# tfcard_shield.net
KiCad netlist of a schematic drawn in Altium Designer
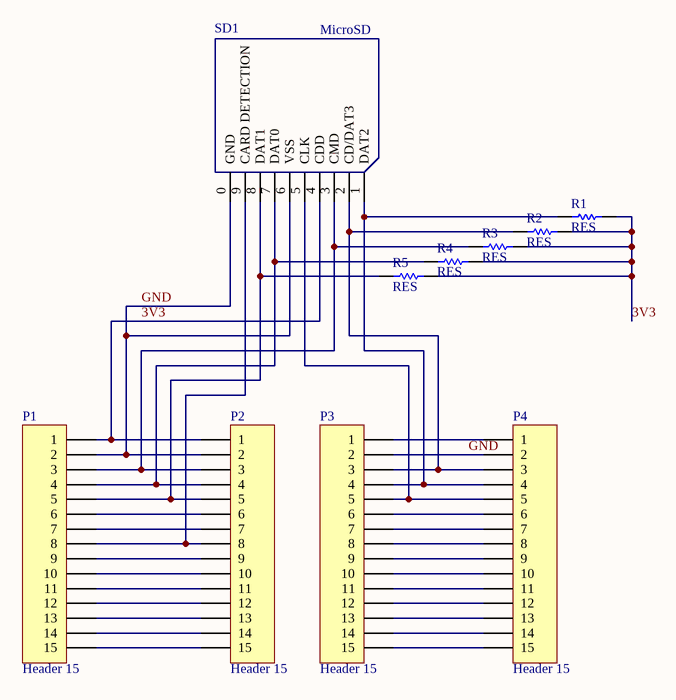
[diagram p0: tfcard_shield.SchDoc]

(export (version "E")
  (design (tool "Eeschema 10.0.6"))
  (components
    (comp (ref "P1")
      (value "Header 15")
      (footprint "HDR1X15")
      (description "Header, 15-Pin")
      (fields (field (name "PUBLISHER") "Altium Limited"))
      (libsource (lib "") (part "Header 15_1"))
    )
    (comp (ref "P2")
      (value "Header 15")
      (footprint "HDR1X15")
      (description "Header, 15-Pin")
      (fields (field (name "PUBLISHER") "Altium Limited"))
      (libsource (lib "Miscellaneous Connectors") (part "Header 15"))
    )
    (comp (ref "P3")
      (value "Header 15")
      (footprint "HDR1X15")
      (description "Header, 15-Pin")
      (fields (field (name "PUBLISHER") "Altium Limited"))
      (libsource (lib "") (part "Header 15_1"))
    )
    (comp (ref "P4")
      (value "Header 15")
      (footprint "HDR1X15")
      (description "Header, 15-Pin")
      (fields (field (name "PUBLISHER") "Altium Limited"))
      (libsource (lib "Miscellaneous Connectors") (part "Header 15"))
    )
    (comp (ref "R1") (value "RES") (footprint "0603R") (libsource (lib "电阻") (part "RES")))
    (comp (ref "R2") (value "RES") (footprint "0603R") (libsource (lib "电阻") (part "RES")))
    (comp (ref "R3") (value "RES") (footprint "0603R") (libsource (lib "电阻") (part "RES")))
    (comp (ref "R4") (value "RES") (footprint "0603R") (libsource (lib "电阻") (part "RES")))
    (comp (ref "R5") (value "RES") (footprint "0603R") (libsource (lib "电阻") (part "RES")))
    (comp (ref "SD1") (value "MicroSD") (footprint "Micro SD") (libsource (lib "SD Card") (part "MicroSD")))
  )
  (nets
    (net (code "1") (name "/3V3") (class "Default")
      (node (ref "P1") (pin "1") (pinfunction "1_1") (pintype "passive"))
      (node (ref "P2") (pin "1") (pinfunction "1_1") (pintype "passive"))
      (node (ref "R1") (pin "2") (pinfunction "2_2") (pintype "passive"))
      (node (ref "R2") (pin "2") (pinfunction "2_2") (pintype "passive"))
      (node (ref "R3") (pin "2") (pinfunction "2_2") (pintype "passive"))
      (node (ref "R4") (pin "2") (pinfunction "2_2") (pintype "passive"))
      (node (ref "R5") (pin "2") (pinfunction "2_2") (pintype "passive"))
      (node (ref "SD1") (pin "4") (pinfunction "CDD_4") (pintype "passive"))
    )
    (net (code "2") (name "/GND") (class "Default")
      (node (ref "P1") (pin "2") (pinfunction "2_2") (pintype "passive"))
      (node (ref "P2") (pin "2") (pinfunction "2_2") (pintype "passive"))
      (node (ref "P3") (pin "2") (pinfunction "2_2") (pintype "passive"))
      (node (ref "P4") (pin "2") (pinfunction "2_2") (pintype "passive"))
      (node (ref "SD1") (pin "0") (pinfunction "GND_0") (pintype "passive"))
      (node (ref "SD1") (pin "6") (pinfunction "VSS_6") (pintype "passive"))
    )
    (net (code "3") (name "Net-(P1-Pad6)") (class "Default")
      (node (ref "P1") (pin "6") (pinfunction "6_6") (pintype "passive"))
      (node (ref "P2") (pin "6") (pinfunction "6_6") (pintype "passive"))
    )
    (net (code "4") (name "Net-(P1-Pad7)") (class "Default")
      (node (ref "P1") (pin "7") (pinfunction "7_7") (pintype "passive"))
      (node (ref "P2") (pin "7") (pinfunction "7_7") (pintype "passive"))
    )
    (net (code "5") (name "Net-(P1-Pad9)") (class "Default")
      (node (ref "P1") (pin "9") (pinfunction "9_9") (pintype "passive"))
      (node (ref "P2") (pin "9") (pinfunction "9_9") (pintype "passive"))
    )
    (net (code "6") (name "Net-(P1-Pad10)") (class "Default")
      (node (ref "P1") (pin "10") (pinfunction "10_10") (pintype "passive"))
      (node (ref "P2") (pin "10") (pinfunction "10_10") (pintype "passive"))
    )
    (net (code "7") (name "Net-(P1-Pad11)") (class "Default")
      (node (ref "P1") (pin "11") (pinfunction "11_11") (pintype "passive"))
      (node (ref "P2") (pin "11") (pinfunction "11_11") (pintype "passive"))
    )
    (net (code "8") (name "Net-(P1-Pad12)") (class "Default")
      (node (ref "P1") (pin "12") (pinfunction "12_12") (pintype "passive"))
      (node (ref "P2") (pin "12") (pinfunction "12_12") (pintype "passive"))
    )
    (net (code "9") (name "Net-(P1-Pad13)") (class "Default")
      (node (ref "P1") (pin "13") (pinfunction "13_13") (pintype "passive"))
      (node (ref "P2") (pin "13") (pinfunction "13_13") (pintype "passive"))
    )
    (net (code "10") (name "Net-(P1-Pad14)") (class "Default")
      (node (ref "P1") (pin "14") (pinfunction "14_14") (pintype "passive"))
      (node (ref "P2") (pin "14") (pinfunction "14_14") (pintype "passive"))
    )
    (net (code "11") (name "Net-(P1-Pad15)") (class "Default")
      (node (ref "P1") (pin "15") (pinfunction "15_15") (pintype "passive"))
      (node (ref "P2") (pin "15") (pinfunction "15_15") (pintype "passive"))
    )
    (net (code "12") (name "Net-(P3-Pad1)") (class "Default")
      (node (ref "P3") (pin "1") (pinfunction "1_1") (pintype "passive"))
      (node (ref "P4") (pin "1") (pinfunction "1_1") (pintype "passive"))
    )
    (net (code "13") (name "Net-(P3-Pad6)") (class "Default")
      (node (ref "P3") (pin "6") (pinfunction "6_6") (pintype "passive"))
      (node (ref "P4") (pin "6") (pinfunction "6_6") (pintype "passive"))
    )
    (net (code "14") (name "Net-(P3-Pad7)") (class "Default")
      (node (ref "P3") (pin "7") (pinfunction "7_7") (pintype "passive"))
      (node (ref "P4") (pin "7") (pinfunction "7_7") (pintype "passive"))
    )
    (net (code "15") (name "Net-(P3-Pad8)") (class "Default")
      (node (ref "P3") (pin "8") (pinfunction "8_8") (pintype "passive"))
      (node (ref "P4") (pin "8") (pinfunction "8_8") (pintype "passive"))
    )
    (net (code "16") (name "Net-(P3-Pad9)") (class "Default")
      (node (ref "P3") (pin "9") (pinfunction "9_9") (pintype "passive"))
      (node (ref "P4") (pin "9") (pinfunction "9_9") (pintype "passive"))
    )
    (net (code "17") (name "Net-(P3-Pad10)") (class "Default")
      (node (ref "P3") (pin "10") (pinfunction "10_10") (pintype "passive"))
      (node (ref "P4") (pin "10") (pinfunction "10_10") (pintype "passive"))
    )
    (net (code "18") (name "Net-(P3-Pad11)") (class "Default")
      (node (ref "P3") (pin "11") (pinfunction "11_11") (pintype "passive"))
      (node (ref "P4") (pin "11") (pinfunction "11_11") (pintype "passive"))
    )
    (net (code "19") (name "Net-(P3-Pad12)") (class "Default")
      (node (ref "P3") (pin "12") (pinfunction "12_12") (pintype "passive"))
      (node (ref "P4") (pin "12") (pinfunction "12_12") (pintype "passive"))
    )
    (net (code "20") (name "Net-(P3-Pad13)") (class "Default")
      (node (ref "P3") (pin "13") (pinfunction "13_13") (pintype "passive"))
      (node (ref "P4") (pin "13") (pinfunction "13_13") (pintype "passive"))
    )
    (net (code "21") (name "Net-(P3-Pad14)") (class "Default")
      (node (ref "P3") (pin "14") (pinfunction "14_14") (pintype "passive"))
      (node (ref "P4") (pin "14") (pinfunction "14_14") (pintype "passive"))
    )
    (net (code "22") (name "Net-(P3-Pad15)") (class "Default")
      (node (ref "P3") (pin "15") (pinfunction "15_15") (pintype "passive"))
      (node (ref "P4") (pin "15") (pinfunction "15_15") (pintype "passive"))
    )
    (net (code "23") (name "Net-(SD1-CARD_DETECTION)") (class "Default")
      (node (ref "P1") (pin "8") (pinfunction "8_8") (pintype "passive"))
      (node (ref "P2") (pin "8") (pinfunction "8_8") (pintype "passive"))
      (node (ref "SD1") (pin "9") (pinfunction "CARD_DETECTION_9") (pintype "passive"))
    )
    (net (code "24") (name "Net-(SD1-CD{slash}DAT3)") (class "Default")
      (node (ref "P3") (pin "3") (pinfunction "3_3") (pintype "passive"))
      (node (ref "P4") (pin "3") (pinfunction "3_3") (pintype "passive"))
      (node (ref "R2") (pin "1") (pinfunction "1_1") (pintype "passive"))
      (node (ref "SD1") (pin "2") (pinfunction "CD/DAT3_2") (pintype "passive"))
    )
    (net (code "25") (name "Net-(SD1-CLK)") (class "Default")
      (node (ref "P3") (pin "5") (pinfunction "5_5") (pintype "passive"))
      (node (ref "P4") (pin "5") (pinfunction "5_5") (pintype "passive"))
      (node (ref "SD1") (pin "5") (pinfunction "CLK_5") (pintype "passive"))
    )
    (net (code "26") (name "Net-(SD1-CMD)") (class "Default")
      (node (ref "P1") (pin "3") (pinfunction "3_3") (pintype "passive"))
      (node (ref "P2") (pin "3") (pinfunction "3_3") (pintype "passive"))
      (node (ref "R3") (pin "1") (pinfunction "1_1") (pintype "passive"))
      (node (ref "SD1") (pin "3") (pinfunction "CMD_3") (pintype "passive"))
    )
    (net (code "27") (name "Net-(SD1-DAT0)") (class "Default")
      (node (ref "P1") (pin "4") (pinfunction "4_4") (pintype "passive"))
      (node (ref "P2") (pin "4") (pinfunction "4_4") (pintype "passive"))
      (node (ref "R4") (pin "1") (pinfunction "1_1") (pintype "passive"))
      (node (ref "SD1") (pin "7") (pinfunction "DAT0_7") (pintype "passive"))
    )
    (net (code "28") (name "Net-(SD1-DAT1)") (class "Default")
      (node (ref "P1") (pin "5") (pinfunction "5_5") (pintype "passive"))
      (node (ref "P2") (pin "5") (pinfunction "5_5") (pintype "passive"))
      (node (ref "R5") (pin "1") (pinfunction "1_1") (pintype "passive"))
      (node (ref "SD1") (pin "8") (pinfunction "DAT1_8") (pintype "passive"))
    )
    (net (code "29") (name "Net-(SD1-DAT2)") (class "Default")
      (node (ref "P3") (pin "4") (pinfunction "4_4") (pintype "passive"))
      (node (ref "P4") (pin "4") (pinfunction "4_4") (pintype "passive"))
      (node (ref "R1") (pin "1") (pinfunction "1_1") (pintype "passive"))
      (node (ref "SD1") (pin "1") (pinfunction "DAT2_1") (pintype "passive"))
    )
  )
)
